# flex_probe.net
KiCad netlist of a schematic drawn in EAGLE
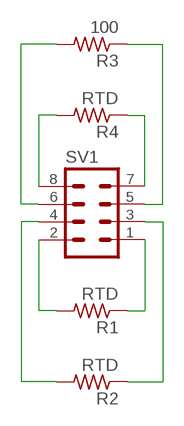
[diagram p0: schematic, sheet 1]

(export (version "E")
  (design (tool "Eeschema 10.0.6"))
  (components
    (comp (ref "R1")
      (value "RTD")
      (footprint "eagle-import:R0603")
      (libsource (lib "eagle-import") (part "R-US_R0603"))
    )
    (comp (ref "R2")
      (value "RTD")
      (footprint "eagle-import:R0603")
      (libsource (lib "eagle-import") (part "R-US_R0603"))
    )
    (comp (ref "R3")
      (value "100")
      (footprint "eagle-import:R0603")
      (libsource (lib "eagle-import") (part "R-US_R0603"))
    )
    (comp (ref "R4")
      (value "RTD")
      (footprint "eagle-import:R0603")
      (libsource (lib "eagle-import") (part "R-US_R0603"))
    )
    (comp (ref "SV1")
      (value "MA04-2")
      (footprint "eagle-import:MA04-2")
      (libsource (lib "eagle-import") (part "MA04-2"))
    )
  )
  (nets
    (net (code "1") (name "Net-(R1-Pad1)") (class "Default")
      (node (ref "R1") (pin "1") (pinfunction "1_1") (pintype "passive"))
      (node (ref "SV1") (pin "1") (pinfunction "1_1") (pintype "passive"))
    )
    (net (code "2") (name "Net-(R1-Pad2)") (class "Default")
      (node (ref "R1") (pin "2") (pinfunction "2_2") (pintype "passive"))
      (node (ref "SV1") (pin "2") (pinfunction "2_2") (pintype "passive"))
    )
    (net (code "3") (name "Net-(R2-Pad1)") (class "Default")
      (node (ref "R2") (pin "1") (pinfunction "1_1") (pintype "passive"))
      (node (ref "SV1") (pin "3") (pinfunction "3_3") (pintype "passive"))
    )
    (net (code "4") (name "Net-(R2-Pad2)") (class "Default")
      (node (ref "R2") (pin "2") (pinfunction "2_2") (pintype "passive"))
      (node (ref "SV1") (pin "4") (pinfunction "4_4") (pintype "passive"))
    )
    (net (code "5") (name "Net-(R3-Pad1)") (class "Default")
      (node (ref "R3") (pin "1") (pinfunction "1_1") (pintype "passive"))
      (node (ref "SV1") (pin "5") (pinfunction "5_5") (pintype "passive"))
    )
    (net (code "6") (name "Net-(R3-Pad2)") (class "Default")
      (node (ref "R3") (pin "2") (pinfunction "2_2") (pintype "passive"))
      (node (ref "SV1") (pin "6") (pinfunction "6_6") (pintype "passive"))
    )
    (net (code "7") (name "Net-(R4-Pad1)") (class "Default")
      (node (ref "R4") (pin "1") (pinfunction "1_1") (pintype "passive"))
      (node (ref "SV1") (pin "7") (pinfunction "7_7") (pintype "passive"))
    )
    (net (code "8") (name "Net-(R4-Pad2)") (class "Default")
      (node (ref "R4") (pin "2") (pinfunction "2_2") (pintype "passive"))
      (node (ref "SV1") (pin "8") (pinfunction "8_8") (pintype "passive"))
    )
  )
)
